# ad8495Amp.net
KiCad netlist of a schematic drawn in EAGLE
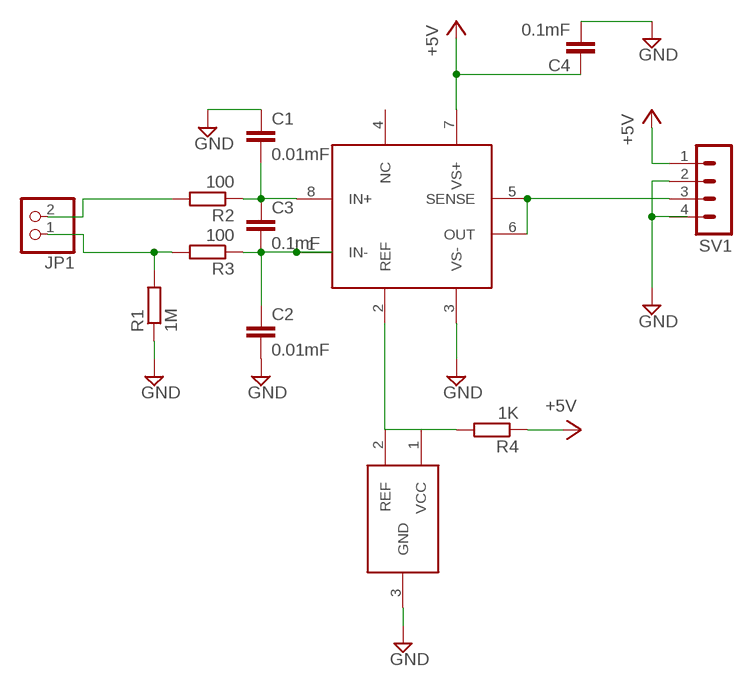
[diagram p0: schematic, sheet 1]

(export (version "E")
  (design (tool "Eeschema 10.0.6"))
  (components
    (comp (ref "C1")
      (value "0.01mF")
      (footprint "eagle-import:C1206")
      (libsource (lib "eagle-import") (part "C-EUC1206"))
    )
    (comp (ref "C2")
      (value "0.01mF")
      (footprint "eagle-import:C1206")
      (libsource (lib "eagle-import") (part "C-EUC1206"))
    )
    (comp (ref "C3")
      (value "0.1mF")
      (footprint "eagle-import:C1206")
      (libsource (lib "eagle-import") (part "C-EUC1206"))
    )
    (comp (ref "C4")
      (value "0.1mF")
      (footprint "eagle-import:C1206")
      (libsource (lib "eagle-import") (part "C-EUC1206"))
    )
    (comp (ref "JP1")
      (value "PINHD-1X2")
      (footprint "eagle-import:1X02")
      (libsource (lib "eagle-import") (part "PINHD-1X2"))
    )
    (comp (ref "R1")
      (value "1M")
      (footprint "eagle-import:R1206")
      (libsource (lib "eagle-import") (part "R-EU_R1206"))
    )
    (comp (ref "R2")
      (value "100")
      (footprint "eagle-import:R1206")
      (libsource (lib "eagle-import") (part "R-EU_R1206"))
    )
    (comp (ref "R3")
      (value "100")
      (footprint "eagle-import:R1206")
      (libsource (lib "eagle-import") (part "R-EU_R1206"))
    )
    (comp (ref "R4")
      (value "1K")
      (footprint "eagle-import:R1206")
      (libsource (lib "eagle-import") (part "R-EU_R1206"))
    )
    (comp (ref "SV1")
      (value "MA04-1")
      (footprint "eagle-import:MA04-1")
      (libsource (lib "eagle-import") (part "MA04-1"))
    )
    (comp (ref "U$1")
      (value "AD8495MSOP8")
      (footprint "eagle-import:MSOP8")
      (libsource (lib "eagle-import") (part "AD8495MSOP8"))
    )
    (comp (ref "U$2")
      (value "TLVH431TLVH431")
      (footprint "eagle-import:SOT23-R")
      (libsource (lib "eagle-import") (part "TLVH431TLVH431"))
    )
  )
  (nets
    (net (code "1") (name "+5V") (class "Default")
      (node (ref "C4") (pin "1") (pinfunction "1_1") (pintype "passive"))
      (node (ref "R4") (pin "1") (pinfunction "1_1") (pintype "passive"))
      (node (ref "SV1") (pin "1") (pinfunction "1_1") (pintype "passive"))
      (node (ref "U$1") (pin "7") (pinfunction "VS+_7") (pintype "power_in"))
    )
    (net (code "2") (name "GND") (class "Default")
      (node (ref "C1") (pin "1") (pinfunction "1_1") (pintype "passive"))
      (node (ref "C2") (pin "2") (pinfunction "2_2") (pintype "passive"))
      (node (ref "C4") (pin "2") (pinfunction "2_2") (pintype "passive"))
      (node (ref "R1") (pin "1") (pinfunction "1_1") (pintype "passive"))
      (node (ref "SV1") (pin "2") (pinfunction "2_2") (pintype "passive"))
      (node (ref "U$1") (pin "3") (pinfunction "VS-_3") (pintype "power_in"))
      (node (ref "U$2") (pin "3") (pinfunction "GND_3") (pintype "power_in"))
    )
    (net (code "3") (name "Net-(JP1-Pad1)") (class "Default")
      (node (ref "JP1") (pin "1") (pinfunction "1_1") (pintype "passive"))
      (node (ref "R1") (pin "2") (pinfunction "2_2") (pintype "passive"))
      (node (ref "R3") (pin "2") (pinfunction "2_2") (pintype "passive"))
    )
    (net (code "4") (name "Net-(JP1-Pad2)") (class "Default")
      (node (ref "JP1") (pin "2") (pinfunction "2_2") (pintype "passive"))
      (node (ref "R2") (pin "2") (pinfunction "2_2") (pintype "passive"))
    )
    (net (code "5") (name "Net-(U$1-IN+)") (class "Default")
      (node (ref "C1") (pin "2") (pinfunction "2_2") (pintype "passive"))
      (node (ref "C3") (pin "1") (pinfunction "1_1") (pintype "passive"))
      (node (ref "R2") (pin "1") (pinfunction "1_1") (pintype "passive"))
      (node (ref "U$1") (pin "8") (pinfunction "IN+_8") (pintype "input"))
    )
    (net (code "6") (name "Net-(U$1-IN-)") (class "Default")
      (node (ref "C2") (pin "1") (pinfunction "1_1") (pintype "passive"))
      (node (ref "C3") (pin "2") (pinfunction "2_2") (pintype "passive"))
      (node (ref "R3") (pin "1") (pinfunction "1_1") (pintype "passive"))
      (node (ref "U$1") (pin "1") (pinfunction "IN-_1") (pintype "input"))
    )
    (net (code "7") (name "Net-(U$1-OUT)") (class "Default")
      (node (ref "SV1") (pin "3") (pinfunction "3_3") (pintype "passive"))
      (node (ref "U$1") (pin "5") (pinfunction "SENSE_5") (pintype "bidirectional"))
      (node (ref "U$1") (pin "6") (pinfunction "OUT_6") (pintype "output"))
    )
    (net (code "8") (name "Net-(U$1-REF)") (class "Default")
      (node (ref "R4") (pin "2") (pinfunction "2_2") (pintype "passive"))
      (node (ref "U$1") (pin "2") (pinfunction "REF_2") (pintype "bidirectional"))
      (node (ref "U$2") (pin "1") (pinfunction "VCC_1") (pintype "power_in"))
      (node (ref "U$2") (pin "2") (pinfunction "REF_2") (pintype "output"))
    )
    (net (code "9") (name "unconnected-(SV1-Pad4)") (class "Default")
      (node (ref "SV1") (pin "4") (pinfunction "4_4") (pintype "passive"))
    )
    (net (code "10") (name "unconnected-(U$1-NC-Pad4)") (class "Default")
      (node (ref "U$1") (pin "4") (pinfunction "NC_4") (pintype "no_connect"))
    )
  )
)
